# sensor_board.net
KiCad netlist of a schematic drawn in EAGLE
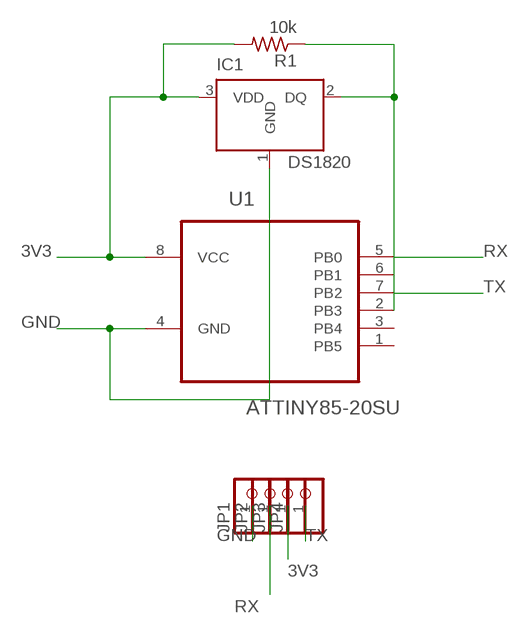
[diagram p0: schematic, sheet 1]

(export (version "E")
  (design (tool "Eeschema 10.0.6"))
  (components
    (comp (ref "IC1")
      (value "DS1820")
      (footprint "eagle-import:TO-92")
      (libsource (lib "eagle-import") (part "DS1820"))
    )
    (comp (ref "JP1")
      (value "PINHD-1X1")
      (footprint "eagle-import:1X01")
      (libsource (lib "eagle-import") (part "PINHD-1X1"))
    )
    (comp (ref "JP2")
      (value "PINHD-1X1")
      (footprint "eagle-import:1X01")
      (libsource (lib "eagle-import") (part "PINHD-1X1"))
    )
    (comp (ref "JP3")
      (value "PINHD-1X1")
      (footprint "eagle-import:1X01")
      (libsource (lib "eagle-import") (part "PINHD-1X1"))
    )
    (comp (ref "JP4")
      (value "PINHD-1X1")
      (footprint "eagle-import:1X01")
      (libsource (lib "eagle-import") (part "PINHD-1X1"))
    )
    (comp (ref "R1")
      (value "10k")
      (footprint "eagle-import:R1206")
      (libsource (lib "eagle-import") (part "RES-US1206"))
    )
    (comp (ref "U1")
      (value "ATTINY85-20SU")
      (footprint "eagle-import:SOIC127P798X216-8N")
      (libsource (lib "eagle-import") (part "ATTINY85-20SU"))
    )
  )
  (nets
    (net (code "1") (name "/3V3") (class "Default")
      (node (ref "IC1") (pin "3") (pinfunction "VDD_3") (pintype "input"))
      (node (ref "JP3") (pin "1") (pinfunction "1_1") (pintype "passive"))
      (node (ref "R1") (pin "2") (pinfunction "2_2") (pintype "passive"))
      (node (ref "U1") (pin "8") (pinfunction "VCC_8") (pintype "power_in"))
    )
    (net (code "2") (name "/GND") (class "Default")
      (node (ref "IC1") (pin "1") (pinfunction "GND_1") (pintype "power_in"))
      (node (ref "JP1") (pin "1") (pinfunction "1_1") (pintype "passive"))
      (node (ref "U1") (pin "4") (pinfunction "GND_4") (pintype "passive"))
    )
    (net (code "3") (name "/RX") (class "Default")
      (node (ref "JP2") (pin "1") (pinfunction "1_1") (pintype "passive"))
      (node (ref "U1") (pin "5") (pinfunction "PB0_5") (pintype "bidirectional"))
    )
    (net (code "4") (name "/TX") (class "Default")
      (node (ref "JP4") (pin "1") (pinfunction "1_1") (pintype "passive"))
      (node (ref "U1") (pin "7") (pinfunction "PB2_7") (pintype "bidirectional"))
    )
    (net (code "5") (name "Net-(IC1-DQ)") (class "Default")
      (node (ref "IC1") (pin "2") (pinfunction "DQ_2") (pintype "output"))
      (node (ref "R1") (pin "1") (pinfunction "1_1") (pintype "passive"))
      (node (ref "U1") (pin "2") (pinfunction "PB3_2") (pintype "bidirectional"))
    )
    (net (code "6") (name "unconnected-(U1-PB1-Pad6)") (class "Default")
      (node (ref "U1") (pin "6") (pinfunction "PB1_6") (pintype "bidirectional"))
    )
    (net (code "7") (name "unconnected-(U1-PB4-Pad3)") (class "Default")
      (node (ref "U1") (pin "3") (pinfunction "PB4_3") (pintype "bidirectional"))
    )
    (net (code "8") (name "unconnected-(U1-PB5-Pad1)") (class "Default")
      (node (ref "U1") (pin "1") (pinfunction "PB5_1") (pintype "bidirectional"))
    )
  )
)
